# Glucometer-I_C_-_RF_Module.net
KiCad netlist of a schematic drawn in Altium Designer
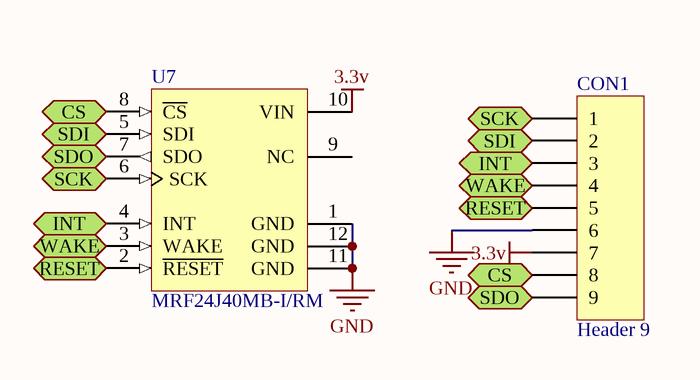
[diagram p0: Glucometer-I.C.- RF Module.SchDoc]

(export (version "E")
  (design (tool "Eeschema 10.0.6"))
  (components
    (comp (ref "CON1")
      (value "Header 9")
      (footprint "HDR1X9")
      (description "Header, 9-Pin")
      (fields (field (name "PUBLISHER") "Altium Limited"))
      (libsource (lib "Miscellaneous Connectors") (part "Header 9"))
    )
    (comp (ref "U7")
      (value "MRF24J40MB-I/RM")
      (footprint "MRF24J40MB")
      (description "2.4 GHz IEEE Std. 802.15.4, 20 dBm RF Transceiver 12-Pin Module, Industrial Temperature")
      (fields (field (name "PUBLISHER") "Altium Limited"))
      (libsource (lib "Microchip Wireless Radio Frequency") (part "MRF24J40MB-I/RM"))
    )
  )
  (nets
    (net (code "1") (name "/CS") (class "Default")
      (node (ref "CON1") (pin "8") (pinfunction "8_8") (pintype "passive"))
      (node (ref "U7") (pin "8") (pinfunction "~{CS}_8") (pintype "input"))
    )
    (net (code "2") (name "/INT") (class "Default")
      (node (ref "CON1") (pin "3") (pinfunction "3_3") (pintype "passive"))
      (node (ref "U7") (pin "4") (pinfunction "INT_4") (pintype "input"))
    )
    (net (code "3") (name "/RESET") (class "Default")
      (node (ref "CON1") (pin "5") (pinfunction "5_5") (pintype "passive"))
      (node (ref "U7") (pin "2") (pinfunction "~{RESET}_2") (pintype "input"))
    )
    (net (code "4") (name "/SCK") (class "Default")
      (node (ref "CON1") (pin "1") (pinfunction "1_1") (pintype "passive"))
      (node (ref "U7") (pin "6") (pinfunction "SCK_6") (pintype "input"))
    )
    (net (code "5") (name "/SDI") (class "Default")
      (node (ref "CON1") (pin "2") (pinfunction "2_2") (pintype "passive"))
      (node (ref "U7") (pin "5") (pinfunction "SDI_5") (pintype "input"))
    )
    (net (code "6") (name "/SDO") (class "Default")
      (node (ref "CON1") (pin "9") (pinfunction "9_9") (pintype "passive"))
      (node (ref "U7") (pin "7") (pinfunction "SDO_7") (pintype "output"))
    )
    (net (code "7") (name "/WAKE") (class "Default")
      (node (ref "CON1") (pin "4") (pinfunction "4_4") (pintype "passive"))
      (node (ref "U7") (pin "3") (pinfunction "WAKE_3") (pintype "input"))
    )
    (net (code "8") (name "3.3v") (class "Default")
      (node (ref "CON1") (pin "7") (pinfunction "7_7") (pintype "passive"))
      (node (ref "U7") (pin "10") (pinfunction "VIN_10") (pintype "power_in"))
    )
    (net (code "9") (name "GND") (class "Default")
      (node (ref "CON1") (pin "6") (pinfunction "6_6") (pintype "passive"))
      (node (ref "U7") (pin "1") (pinfunction "GND_1") (pintype "power_in"))
      (node (ref "U7") (pin "11") (pinfunction "GND_11") (pintype "power_in"))
      (node (ref "U7") (pin "12") (pinfunction "GND_12") (pintype "power_in"))
    )
    (net (code "10") (name "unconnected-(U7-NC-Pad9)") (class "Default")
      (node (ref "U7") (pin "9") (pinfunction "NC_9") (pintype "passive"))
    )
  )
)
